# Components.net
KiCad netlist of a schematic drawn in EAGLE
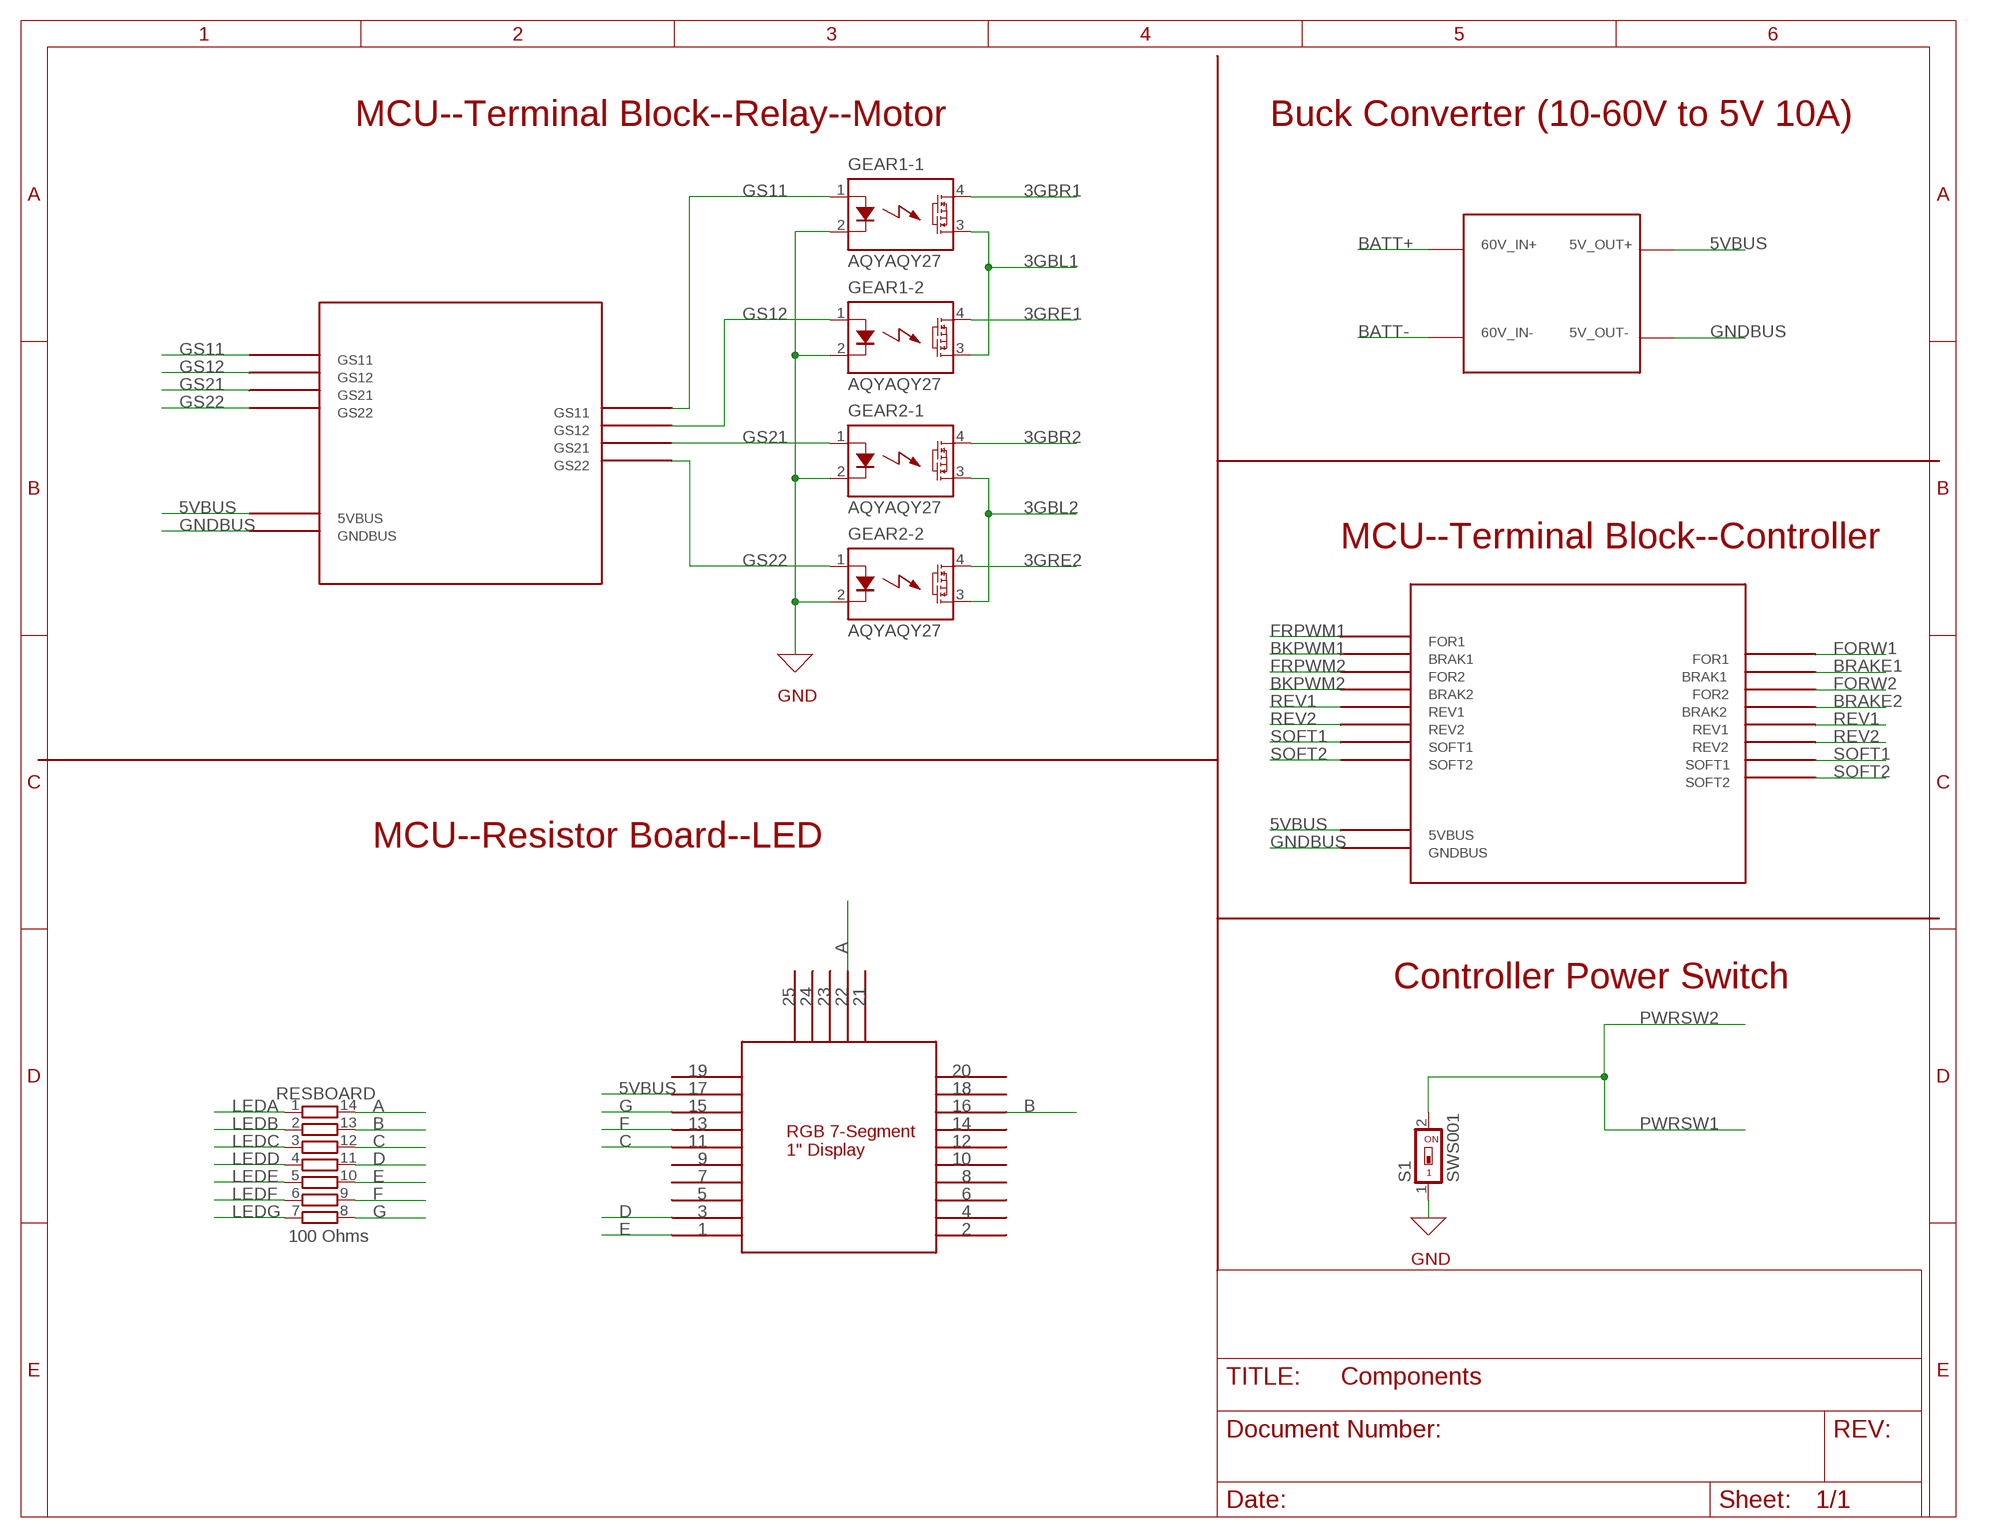
[diagram p0: schematic, sheet 1]

(export (version "E")
  (design (tool "Eeschema 10.0.6"))
  (components
    (comp (ref "GEAR1-1")
      (value "AQYAQY27")
      (footprint "eagle-import:AQY27")
      (libsource (lib "eagle-import") (part "AQYAQY27"))
    )
    (comp (ref "GEAR1-2")
      (value "AQYAQY27")
      (footprint "eagle-import:AQY27")
      (libsource (lib "eagle-import") (part "AQYAQY27"))
    )
    (comp (ref "GEAR2-1")
      (value "AQYAQY27")
      (footprint "eagle-import:AQY27")
      (libsource (lib "eagle-import") (part "AQYAQY27"))
    )
    (comp (ref "GEAR2-2")
      (value "AQYAQY27")
      (footprint "eagle-import:AQY27")
      (libsource (lib "eagle-import") (part "AQYAQY27"))
    )
    (comp (ref "RESBOARD")
      (value "100 Ohms")
      (footprint "eagle-import:4814P")
      (fields (field (name "MF") "BOURNS, INC.") (field (name "MPN") "4814P-T01-104LF"))
      (libsource (lib "eagle-import") (part "4814P-T01"))
    )
    (comp (ref "S1")
      (value "SWS001")
      (footprint "eagle-import:SMS-001")
      (libsource (lib "eagle-import") (part "SWS001"))
    )
  )
  (nets
    (net (code "1") (name "/3GBL1") (class "Default")
      (node (ref "GEAR1-1") (pin "3") (pinfunction "DS2_3") (pintype "passive"))
      (node (ref "GEAR1-2") (pin "3") (pinfunction "DS2_3") (pintype "passive"))
    )
    (net (code "2") (name "/3GBL2") (class "Default")
      (node (ref "GEAR2-1") (pin "3") (pinfunction "DS2_3") (pintype "passive"))
      (node (ref "GEAR2-2") (pin "3") (pinfunction "DS2_3") (pintype "passive"))
    )
    (net (code "3") (name "/3GBR1") (class "Default")
      (node (ref "GEAR1-1") (pin "4") (pinfunction "DS1_4") (pintype "passive"))
    )
    (net (code "4") (name "/3GBR2") (class "Default")
      (node (ref "GEAR2-1") (pin "4") (pinfunction "DS1_4") (pintype "passive"))
    )
    (net (code "5") (name "/3GRE1") (class "Default")
      (node (ref "GEAR1-2") (pin "4") (pinfunction "DS1_4") (pintype "passive"))
    )
    (net (code "6") (name "/3GRE2") (class "Default")
      (node (ref "GEAR2-2") (pin "4") (pinfunction "DS1_4") (pintype "passive"))
    )
    (net (code "8") (name "/A") (class "Default")
      (node (ref "RESBOARD") (pin "14") (pinfunction "14_14") (pintype "passive"))
    )
    (net (code "9") (name "/B") (class "Default")
      (node (ref "RESBOARD") (pin "13") (pinfunction "13_13") (pintype "passive"))
    )
    (net (code "16") (name "/C") (class "Default")
      (node (ref "RESBOARD") (pin "12") (pinfunction "12_12") (pintype "passive"))
    )
    (net (code "17") (name "/D") (class "Default")
      (node (ref "RESBOARD") (pin "11") (pinfunction "11_11") (pintype "passive"))
    )
    (net (code "18") (name "/E") (class "Default")
      (node (ref "RESBOARD") (pin "10") (pinfunction "10_10") (pintype "passive"))
    )
    (net (code "19") (name "/F") (class "Default")
      (node (ref "RESBOARD") (pin "9") (pinfunction "9_9") (pintype "passive"))
    )
    (net (code "24") (name "/G") (class "Default")
      (node (ref "RESBOARD") (pin "8") (pinfunction "8_8") (pintype "passive"))
    )
    (net (code "26") (name "/GS11") (class "Default")
      (node (ref "GEAR1-1") (pin "1") (pinfunction "A_1") (pintype "passive"))
    )
    (net (code "27") (name "/GS12") (class "Default")
      (node (ref "GEAR1-2") (pin "1") (pinfunction "A_1") (pintype "passive"))
    )
    (net (code "28") (name "/GS21") (class "Default")
      (node (ref "GEAR2-1") (pin "1") (pinfunction "A_1") (pintype "passive"))
    )
    (net (code "29") (name "/GS22") (class "Default")
      (node (ref "GEAR2-2") (pin "1") (pinfunction "A_1") (pintype "passive"))
    )
    (net (code "30") (name "/LEDA") (class "Default")
      (node (ref "RESBOARD") (pin "1") (pinfunction "1_1") (pintype "passive"))
    )
    (net (code "31") (name "/LEDB") (class "Default")
      (node (ref "RESBOARD") (pin "2") (pinfunction "2_2") (pintype "passive"))
    )
    (net (code "32") (name "/LEDC") (class "Default")
      (node (ref "RESBOARD") (pin "3") (pinfunction "3_3") (pintype "passive"))
    )
    (net (code "33") (name "/LEDD") (class "Default")
      (node (ref "RESBOARD") (pin "4") (pinfunction "4_4") (pintype "passive"))
    )
    (net (code "34") (name "/LEDE") (class "Default")
      (node (ref "RESBOARD") (pin "5") (pinfunction "5_5") (pintype "passive"))
    )
    (net (code "35") (name "/LEDF") (class "Default")
      (node (ref "RESBOARD") (pin "6") (pinfunction "6_6") (pintype "passive"))
    )
    (net (code "36") (name "/LEDG") (class "Default")
      (node (ref "RESBOARD") (pin "7") (pinfunction "7_7") (pintype "passive"))
    )
    (net (code "37") (name "/PWRSW2") (class "Default")
      (node (ref "S1") (pin "2") (pinfunction "2_2") (pintype "passive"))
    )
    (net (code "42") (name "GND") (class "Default")
      (node (ref "GEAR1-1") (pin "2") (pinfunction "K_2") (pintype "passive"))
      (node (ref "GEAR1-2") (pin "2") (pinfunction "K_2") (pintype "passive"))
      (node (ref "GEAR2-1") (pin "2") (pinfunction "K_2") (pintype "passive"))
      (node (ref "GEAR2-2") (pin "2") (pinfunction "K_2") (pintype "passive"))
      (node (ref "S1") (pin "1") (pinfunction "1_1") (pintype "passive"))
    )
  )
)
